# Main.net
KiCad netlist of a schematic drawn in EAGLE
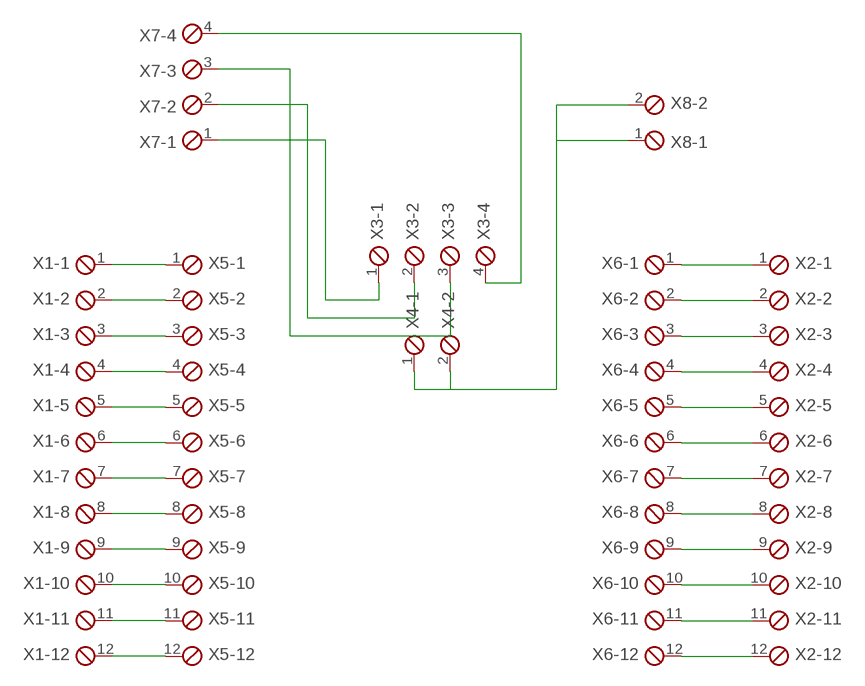
[diagram p0: schematic, sheet 1]

(export (version "E")
  (design (tool "Eeschema 10.0.6"))
  (components
    (comp (ref "X1")
      (value "MPT12")
      (footprint "eagle-import:12POL254")
      (libsource (lib "eagle-import") (part "MPT12"))
    )
    (comp (ref "X2")
      (value "MPT12")
      (footprint "eagle-import:12POL254")
      (libsource (lib "eagle-import") (part "MPT12"))
    )
    (comp (ref "X3")
      (value "MPT4")
      (footprint "eagle-import:4POL254")
      (libsource (lib "eagle-import") (part "MPT4"))
    )
    (comp (ref "X4")
      (value "MPT2")
      (footprint "eagle-import:2POL254")
      (libsource (lib "eagle-import") (part "MPT2"))
    )
    (comp (ref "X5")
      (value "MPT12")
      (footprint "eagle-import:12POL254")
      (libsource (lib "eagle-import") (part "MPT12"))
    )
    (comp (ref "X6")
      (value "MPT12")
      (footprint "eagle-import:12POL254")
      (libsource (lib "eagle-import") (part "MPT12"))
    )
    (comp (ref "X7")
      (value "MPT4")
      (footprint "eagle-import:4POL254")
      (libsource (lib "eagle-import") (part "MPT4"))
    )
    (comp (ref "X8")
      (value "MPT2")
      (footprint "eagle-import:2POL254")
      (libsource (lib "eagle-import") (part "MPT2"))
    )
  )
  (nets
    (net (code "1") (name "Net-(X1-Pad1)") (class "Default")
      (node (ref "X1") (pin "1") (pinfunction "1_1") (pintype "passive"))
      (node (ref "X5") (pin "1") (pinfunction "1_1") (pintype "passive"))
    )
    (net (code "2") (name "Net-(X1B-1)") (class "Default")
      (node (ref "X1") (pin "10") (pinfunction "1_10") (pintype "passive"))
      (node (ref "X5") (pin "10") (pinfunction "1_10") (pintype "passive"))
    )
    (net (code "3") (name "Net-(X1C-1)") (class "Default")
      (node (ref "X1") (pin "11") (pinfunction "1_11") (pintype "passive"))
      (node (ref "X5") (pin "11") (pinfunction "1_11") (pintype "passive"))
    )
    (net (code "4") (name "Net-(X1D-1)") (class "Default")
      (node (ref "X1") (pin "12") (pinfunction "1_12") (pintype "passive"))
      (node (ref "X5") (pin "12") (pinfunction "1_12") (pintype "passive"))
    )
    (net (code "5") (name "Net-(X1E-1)") (class "Default")
      (node (ref "X1") (pin "2") (pinfunction "1_2") (pintype "passive"))
      (node (ref "X5") (pin "2") (pinfunction "1_2") (pintype "passive"))
    )
    (net (code "6") (name "Net-(X1F-1)") (class "Default")
      (node (ref "X1") (pin "3") (pinfunction "1_3") (pintype "passive"))
      (node (ref "X5") (pin "3") (pinfunction "1_3") (pintype "passive"))
    )
    (net (code "7") (name "Net-(X1G-1)") (class "Default")
      (node (ref "X1") (pin "4") (pinfunction "1_4") (pintype "passive"))
      (node (ref "X5") (pin "4") (pinfunction "1_4") (pintype "passive"))
    )
    (net (code "8") (name "Net-(X1H-1)") (class "Default")
      (node (ref "X1") (pin "5") (pinfunction "1_5") (pintype "passive"))
      (node (ref "X5") (pin "5") (pinfunction "1_5") (pintype "passive"))
    )
    (net (code "9") (name "Net-(X1I-1)") (class "Default")
      (node (ref "X1") (pin "6") (pinfunction "1_6") (pintype "passive"))
      (node (ref "X5") (pin "6") (pinfunction "1_6") (pintype "passive"))
    )
    (net (code "10") (name "Net-(X1J-1)") (class "Default")
      (node (ref "X1") (pin "7") (pinfunction "1_7") (pintype "passive"))
      (node (ref "X5") (pin "7") (pinfunction "1_7") (pintype "passive"))
    )
    (net (code "11") (name "Net-(X1K-1)") (class "Default")
      (node (ref "X1") (pin "8") (pinfunction "1_8") (pintype "passive"))
      (node (ref "X5") (pin "8") (pinfunction "1_8") (pintype "passive"))
    )
    (net (code "12") (name "Net-(X1L-1)") (class "Default")
      (node (ref "X1") (pin "9") (pinfunction "1_9") (pintype "passive"))
      (node (ref "X5") (pin "9") (pinfunction "1_9") (pintype "passive"))
    )
    (net (code "13") (name "Net-(X2-Pad1)") (class "Default")
      (node (ref "X2") (pin "1") (pinfunction "1_1") (pintype "passive"))
      (node (ref "X6") (pin "1") (pinfunction "1_1") (pintype "passive"))
    )
    (net (code "14") (name "Net-(X2B-1)") (class "Default")
      (node (ref "X2") (pin "10") (pinfunction "1_10") (pintype "passive"))
      (node (ref "X6") (pin "10") (pinfunction "1_10") (pintype "passive"))
    )
    (net (code "15") (name "Net-(X2C-1)") (class "Default")
      (node (ref "X2") (pin "11") (pinfunction "1_11") (pintype "passive"))
      (node (ref "X6") (pin "11") (pinfunction "1_11") (pintype "passive"))
    )
    (net (code "16") (name "Net-(X2D-1)") (class "Default")
      (node (ref "X2") (pin "12") (pinfunction "1_12") (pintype "passive"))
      (node (ref "X6") (pin "12") (pinfunction "1_12") (pintype "passive"))
    )
    (net (code "17") (name "Net-(X2E-1)") (class "Default")
      (node (ref "X2") (pin "2") (pinfunction "1_2") (pintype "passive"))
      (node (ref "X6") (pin "2") (pinfunction "1_2") (pintype "passive"))
    )
    (net (code "18") (name "Net-(X2F-1)") (class "Default")
      (node (ref "X2") (pin "3") (pinfunction "1_3") (pintype "passive"))
      (node (ref "X6") (pin "3") (pinfunction "1_3") (pintype "passive"))
    )
    (net (code "19") (name "Net-(X2G-1)") (class "Default")
      (node (ref "X2") (pin "4") (pinfunction "1_4") (pintype "passive"))
      (node (ref "X6") (pin "4") (pinfunction "1_4") (pintype "passive"))
    )
    (net (code "20") (name "Net-(X2H-1)") (class "Default")
      (node (ref "X2") (pin "5") (pinfunction "1_5") (pintype "passive"))
      (node (ref "X6") (pin "5") (pinfunction "1_5") (pintype "passive"))
    )
    (net (code "21") (name "Net-(X2I-1)") (class "Default")
      (node (ref "X2") (pin "6") (pinfunction "1_6") (pintype "passive"))
      (node (ref "X6") (pin "6") (pinfunction "1_6") (pintype "passive"))
    )
    (net (code "22") (name "Net-(X2J-1)") (class "Default")
      (node (ref "X2") (pin "7") (pinfunction "1_7") (pintype "passive"))
      (node (ref "X6") (pin "7") (pinfunction "1_7") (pintype "passive"))
    )
    (net (code "23") (name "Net-(X2K-1)") (class "Default")
      (node (ref "X2") (pin "8") (pinfunction "1_8") (pintype "passive"))
      (node (ref "X6") (pin "8") (pinfunction "1_8") (pintype "passive"))
    )
    (net (code "24") (name "Net-(X2L-1)") (class "Default")
      (node (ref "X2") (pin "9") (pinfunction "1_9") (pintype "passive"))
      (node (ref "X6") (pin "9") (pinfunction "1_9") (pintype "passive"))
    )
    (net (code "25") (name "Net-(X3-Pad1)") (class "Default")
      (node (ref "X3") (pin "1") (pinfunction "1_1") (pintype "passive"))
      (node (ref "X7") (pin "1") (pinfunction "1_1") (pintype "passive"))
    )
    (net (code "26") (name "Net-(X3B-1)") (class "Default")
      (node (ref "X3") (pin "2") (pinfunction "1_2") (pintype "passive"))
      (node (ref "X7") (pin "2") (pinfunction "1_2") (pintype "passive"))
    )
    (net (code "27") (name "Net-(X3C-1)") (class "Default")
      (node (ref "X3") (pin "3") (pinfunction "1_3") (pintype "passive"))
      (node (ref "X7") (pin "3") (pinfunction "1_3") (pintype "passive"))
    )
    (net (code "28") (name "Net-(X3D-1)") (class "Default")
      (node (ref "X3") (pin "4") (pinfunction "1_4") (pintype "passive"))
      (node (ref "X7") (pin "4") (pinfunction "1_4") (pintype "passive"))
    )
    (net (code "29") (name "Net-(X4B-1)") (class "Default")
      (node (ref "X4") (pin "1") (pinfunction "1_1") (pintype "passive"))
      (node (ref "X4") (pin "2") (pinfunction "1_2") (pintype "passive"))
      (node (ref "X8") (pin "1") (pinfunction "1_1") (pintype "passive"))
      (node (ref "X8") (pin "2") (pinfunction "1_2") (pintype "passive"))
    )
  )
)
